# Power_Harvesting.net
KiCad netlist of a schematic drawn in Altium Designer
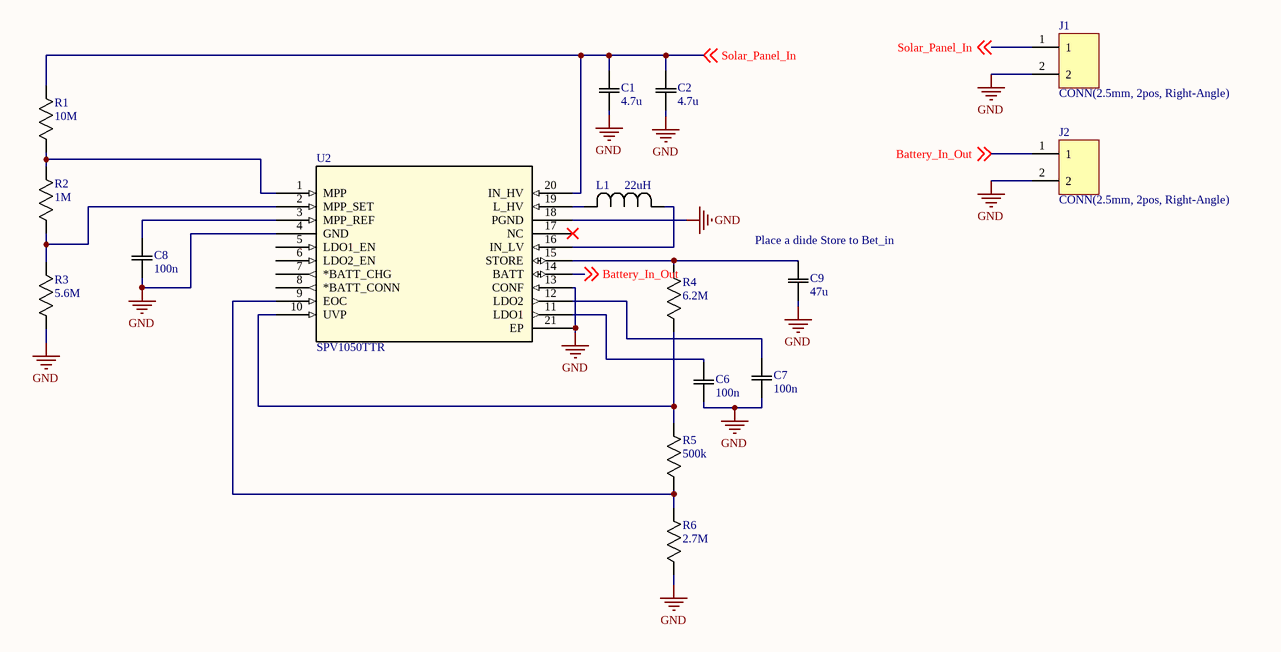
[diagram p0: Power Harvesting.SchDoc]

(export (version "E")
  (design (tool "Eeschema 10.0.6"))
  (components
    (comp (ref "C1")
      (value "4.7u")
      (footprint "CAPC220145_100N_KEM")
      (description "SMD-805")
      (fields
        (field (name "MANUFACTURER_PART_NUMBER") "C0805C105Z4VACTU")
        (field (name "COPYRIGHT") "Copyright (C) 2023 Ultra Librarian. All rights reserved.")
      )
      (libsource (lib "C0805C105Z4VACTU") (part "C0805C105Z4VACTU"))
    )
    (comp (ref "C2")
      (value "4.7u")
      (footprint "CAPC220145_100N_KEM")
      (description "SMD-805")
      (fields
        (field (name "MANUFACTURER_PART_NUMBER") "C0805C105Z4VACTU")
        (field (name "COPYRIGHT") "Copyright (C) 2023 Ultra Librarian. All rights reserved.")
      )
      (libsource (lib "C0805C105Z4VACTU") (part "C0805C105Z4VACTU"))
    )
    (comp (ref "C6")
      (value "100n")
      (footprint "YAG_CC0603_YAG")
      (description "No Description Available")
      (fields
        (field (name "MANUFACTURER_PART_NUMBER") "CC0603KRX7R8BB104")
        (field (name "COPYRIGHT") "Copyright (C) 2024 Ultra Librarian. All rights reserved.")
      )
      (libsource (lib "CC0603KRX7R8BB104") (part "CC0603KRX7R8BB104"))
    )
    (comp (ref "C7")
      (value "100n")
      (footprint "YAG_CC0603_YAG")
      (description "No Description Available")
      (fields
        (field (name "MANUFACTURER_PART_NUMBER") "CC0603KRX7R8BB104")
        (field (name "COPYRIGHT") "Copyright (C) 2024 Ultra Librarian. All rights reserved.")
      )
      (libsource (lib "CC0603KRX7R8BB104") (part "CC0603KRX7R8BB104"))
    )
    (comp (ref "C8")
      (value "100n")
      (footprint "YAG_CC0603_YAG")
      (description "No Description Available")
      (fields
        (field (name "MANUFACTURER_PART_NUMBER") "CC0603KRX7R8BB104")
        (field (name "COPYRIGHT") "Copyright (C) 2024 Ultra Librarian. All rights reserved.")
      )
      (libsource (lib "CC0603KRX7R8BB104") (part "CC0603KRX7R8BB104"))
    )
    (comp (ref "C9")
      (value "47u")
      (footprint "CAPC220145_100N_KEM")
      (description "SMD-805")
      (fields
        (field (name "MANUFACTURER_PART_NUMBER") "C0805C105Z4VACTU")
        (field (name "COPYRIGHT") "Copyright (C) 2023 Ultra Librarian. All rights reserved.")
      )
      (libsource (lib "C0805C105Z4VACTU") (part "C0805C105Z4VACTU"))
    )
    (comp (ref "J1")
      (value "CONN(2.5mm, 2pos, Right-Angle)")
      (footprint "CONN_S2B-PH-K-S_JST")
      (description "No Description Available")
      (libsource (lib "CONN(2.5mm, 2pos, Right-Angle)") (part "CONN(2.5mm, 2pos, Right-Angle)"))
    )
    (comp (ref "J2")
      (value "CONN(2.5mm, 2pos, Right-Angle)")
      (footprint "CONN_S2B-PH-K-S_JST")
      (description "No Description Available")
      (libsource (lib "CONN(2.5mm, 2pos, Right-Angle)") (part "CONN(2.5mm, 2pos, Right-Angle)"))
    )
    (comp (ref "L1")
      (value "22uH")
      (footprint "IND_LPS4018-103MLB_COC")
      (description "No Description Available")
      (fields
        (field (name "MANUFACTURER_PART_NUMBER") "LPS4018-103MLB")
        (field (name "COPYRIGHT") "Copyright (C) 2024 Ultra Librarian. All rights reserved.")
      )
      (libsource (lib "LPS4018-103MLB") (part "LPS4018-103MLB"))
    )
    (comp (ref "R1")
      (value "10M")
      (footprint "RES_CRCW_0805_VIS")
      (description "10K")
      (fields
        (field (name "MANUFACTURER_PART_NUMBER") "CRCW0805100KJNEAC")
        (field (name "COPYRIGHT") "Copyright (C) 2023 Ultra Librarian. All rights reserved.")
      )
      (libsource (lib "CRCW0805100KJNEAC") (part "CRCW0805100KJNEAC"))
    )
    (comp (ref "R2")
      (value "1M")
      (footprint "RES_CRCW_0805_VIS")
      (description "No Description Available")
      (fields
        (field (name "MANUFACTURER_PART_NUMBER") "CRCW0805100KJNEAC")
        (field (name "COPYRIGHT") "Copyright (C) 2023 Ultra Librarian. All rights reserved.")
      )
      (libsource (lib "CRCW0805100KJNEAC") (part "CRCW0805100KJNEAC"))
    )
    (comp (ref "R3")
      (value "5.6M")
      (footprint "RES_CRCW_0805_VIS")
      (description "No Description Available")
      (fields
        (field (name "MANUFACTURER_PART_NUMBER") "CRCW0805100KJNEAC")
        (field (name "COPYRIGHT") "Copyright (C) 2023 Ultra Librarian. All rights reserved.")
      )
      (libsource (lib "CRCW0805100KJNEAC") (part "CRCW0805100KJNEAC"))
    )
    (comp (ref "R4")
      (value "6.2M")
      (footprint "RES_CRCW_0805_VIS")
      (description "No Description Available")
      (fields
        (field (name "MANUFACTURER_PART_NUMBER") "CRCW0805100KJNEAC")
        (field (name "COPYRIGHT") "Copyright (C) 2023 Ultra Librarian. All rights reserved.")
      )
      (libsource (lib "CRCW0805100KJNEAC") (part "CRCW0805100KJNEAC"))
    )
    (comp (ref "R5")
      (value "500k")
      (footprint "RES_CRCW_0805_VIS")
      (description "No Description Available")
      (fields
        (field (name "MANUFACTURER_PART_NUMBER") "CRCW0805100KJNEAC")
        (field (name "COPYRIGHT") "Copyright (C) 2023 Ultra Librarian. All rights reserved.")
      )
      (libsource (lib "CRCW0805100KJNEAC") (part "CRCW0805100KJNEAC"))
    )
    (comp (ref "R6")
      (value "2.7M")
      (footprint "RES_CRCW_0805_VIS")
      (description "No Description Available")
      (fields
        (field (name "MANUFACTURER_PART_NUMBER") "CRCW0805100KJNEAC")
        (field (name "COPYRIGHT") "Copyright (C) 2023 Ultra Librarian. All rights reserved.")
      )
      (libsource (lib "CRCW0805100KJNEAC") (part "CRCW0805100KJNEAC"))
    )
    (comp (ref "U2")
      (value "SPV1050TTR")
      (footprint "VFQFPN20_3X3_STM")
      (description "No Description Available")
      (fields (field (name "COPYRIGHT") "Copyright (C) 2024 Ultra Librarian. All rights reserved."))
      (libsource (lib "SPV1050TTR") (part "SPV1050TTR"))
    )
  )
  (nets
    (net (code "1") (name "Battery_In_Out") (class "Default")
      (node (ref "J2") (pin "1") (pinfunction "1_1") (pintype "passive"))
      (node (ref "U2") (pin "14") (pinfunction "BATT_14") (pintype "bidirectional"))
    )
    (net (code "2") (name "GND") (class "Default")
      (node (ref "C1") (pin "2") (pinfunction "2_2") (pintype "passive"))
      (node (ref "C2") (pin "2") (pinfunction "2_2") (pintype "passive"))
      (node (ref "C6") (pin "1") (pinfunction "1_1") (pintype "passive"))
      (node (ref "C7") (pin "1") (pinfunction "1_1") (pintype "passive"))
      (node (ref "C8") (pin "1") (pinfunction "1_1") (pintype "passive"))
      (node (ref "C9") (pin "2") (pinfunction "2_2") (pintype "passive"))
      (node (ref "J1") (pin "2") (pinfunction "2_2") (pintype "passive"))
      (node (ref "J2") (pin "2") (pinfunction "2_2") (pintype "passive"))
      (node (ref "R3") (pin "1") (pinfunction "1_1") (pintype "passive"))
      (node (ref "R6") (pin "1") (pinfunction "1_1") (pintype "passive"))
      (node (ref "U2") (pin "13") (pinfunction "CONF_13") (pintype "input"))
      (node (ref "U2") (pin "18") (pinfunction "PGND_18") (pintype "power_in"))
      (node (ref "U2") (pin "21") (pinfunction "EP_21") (pintype "power_in"))
      (node (ref "U2") (pin "4") (pinfunction "GND_4") (pintype "power_in"))
    )
    (net (code "3") (name "Net-(U2-EOC)") (class "Default")
      (node (ref "R5") (pin "1") (pinfunction "1_1") (pintype "passive"))
      (node (ref "R6") (pin "2") (pinfunction "2_2") (pintype "passive"))
      (node (ref "U2") (pin "9") (pinfunction "EOC_9") (pintype "input"))
    )
    (net (code "4") (name "Net-(U2-IN_LV)") (class "Default")
      (node (ref "L1") (pin "1") (pinfunction "1_1") (pintype "passive"))
      (node (ref "U2") (pin "16") (pinfunction "IN_LV_16") (pintype "input"))
    )
    (net (code "5") (name "Net-(U2-LDO1)") (class "Default")
      (node (ref "C6") (pin "2") (pinfunction "2_2") (pintype "passive"))
      (node (ref "U2") (pin "11") (pinfunction "LDO1_11") (pintype "output"))
    )
    (net (code "6") (name "Net-(U2-LDO2)") (class "Default")
      (node (ref "C7") (pin "2") (pinfunction "2_2") (pintype "passive"))
      (node (ref "U2") (pin "12") (pinfunction "LDO2_12") (pintype "output"))
    )
    (net (code "7") (name "Net-(U2-L_HV)") (class "Default")
      (node (ref "L1") (pin "2") (pinfunction "2_2") (pintype "passive"))
      (node (ref "U2") (pin "19") (pinfunction "L_HV_19") (pintype "input"))
    )
    (net (code "8") (name "Net-(U2-MPP)") (class "Default")
      (node (ref "R1") (pin "1") (pinfunction "1_1") (pintype "passive"))
      (node (ref "R2") (pin "2") (pinfunction "2_2") (pintype "passive"))
      (node (ref "U2") (pin "1") (pinfunction "MPP_1") (pintype "input"))
    )
    (net (code "9") (name "Net-(U2-MPP_REF)") (class "Default")
      (node (ref "C8") (pin "2") (pinfunction "2_2") (pintype "passive"))
      (node (ref "U2") (pin "3") (pinfunction "MPP_REF_3") (pintype "input"))
    )
    (net (code "10") (name "Net-(U2-MPP_SET)") (class "Default")
      (node (ref "R2") (pin "1") (pinfunction "1_1") (pintype "passive"))
      (node (ref "R3") (pin "2") (pinfunction "2_2") (pintype "passive"))
      (node (ref "U2") (pin "2") (pinfunction "MPP_SET_2") (pintype "input"))
    )
    (net (code "11") (name "Net-(U2-STORE)") (class "Default")
      (node (ref "C9") (pin "1") (pinfunction "1_1") (pintype "passive"))
      (node (ref "R4") (pin "2") (pinfunction "2_2") (pintype "passive"))
      (node (ref "U2") (pin "15") (pinfunction "STORE_15") (pintype "bidirectional"))
    )
    (net (code "12") (name "Net-(U2-UVP)") (class "Default")
      (node (ref "R4") (pin "1") (pinfunction "1_1") (pintype "passive"))
      (node (ref "R5") (pin "2") (pinfunction "2_2") (pintype "passive"))
      (node (ref "U2") (pin "10") (pinfunction "UVP_10") (pintype "input"))
    )
    (net (code "13") (name "Solar_Panel_In") (class "Default")
      (node (ref "C1") (pin "1") (pinfunction "1_1") (pintype "passive"))
      (node (ref "C2") (pin "1") (pinfunction "1_1") (pintype "passive"))
      (node (ref "J1") (pin "1") (pinfunction "1_1") (pintype "passive"))
      (node (ref "R1") (pin "2") (pinfunction "2_2") (pintype "passive"))
      (node (ref "U2") (pin "20") (pinfunction "IN_HV_20") (pintype "input"))
    )
    (net (code "14") (name "unconnected-(U2-*BATT_CHG-Pad7)") (class "Default")
      (node (ref "U2") (pin "7") (pinfunction "*BATT_CHG_7") (pintype "output"))
    )
    (net (code "15") (name "unconnected-(U2-*BATT_CONN-Pad8)") (class "Default")
      (node (ref "U2") (pin "8") (pinfunction "*BATT_CONN_8") (pintype "output"))
    )
    (net (code "16") (name "unconnected-(U2-LDO1_EN-Pad5)") (class "Default")
      (node (ref "U2") (pin "5") (pinfunction "LDO1_EN_5") (pintype "input"))
    )
    (net (code "17") (name "unconnected-(U2-LDO2_EN-Pad6)") (class "Default")
      (node (ref "U2") (pin "6") (pinfunction "LDO2_EN_6") (pintype "input"))
    )
    (net (code "18") (name "unconnected-(U2-NC-Pad17)") (class "Default")
      (node (ref "U2") (pin "17") (pinfunction "NC_17") (pintype "passive+no_connect"))
    )
  )
)
